# 3_-MCU.net
KiCad netlist of a schematic drawn in Altium Designer
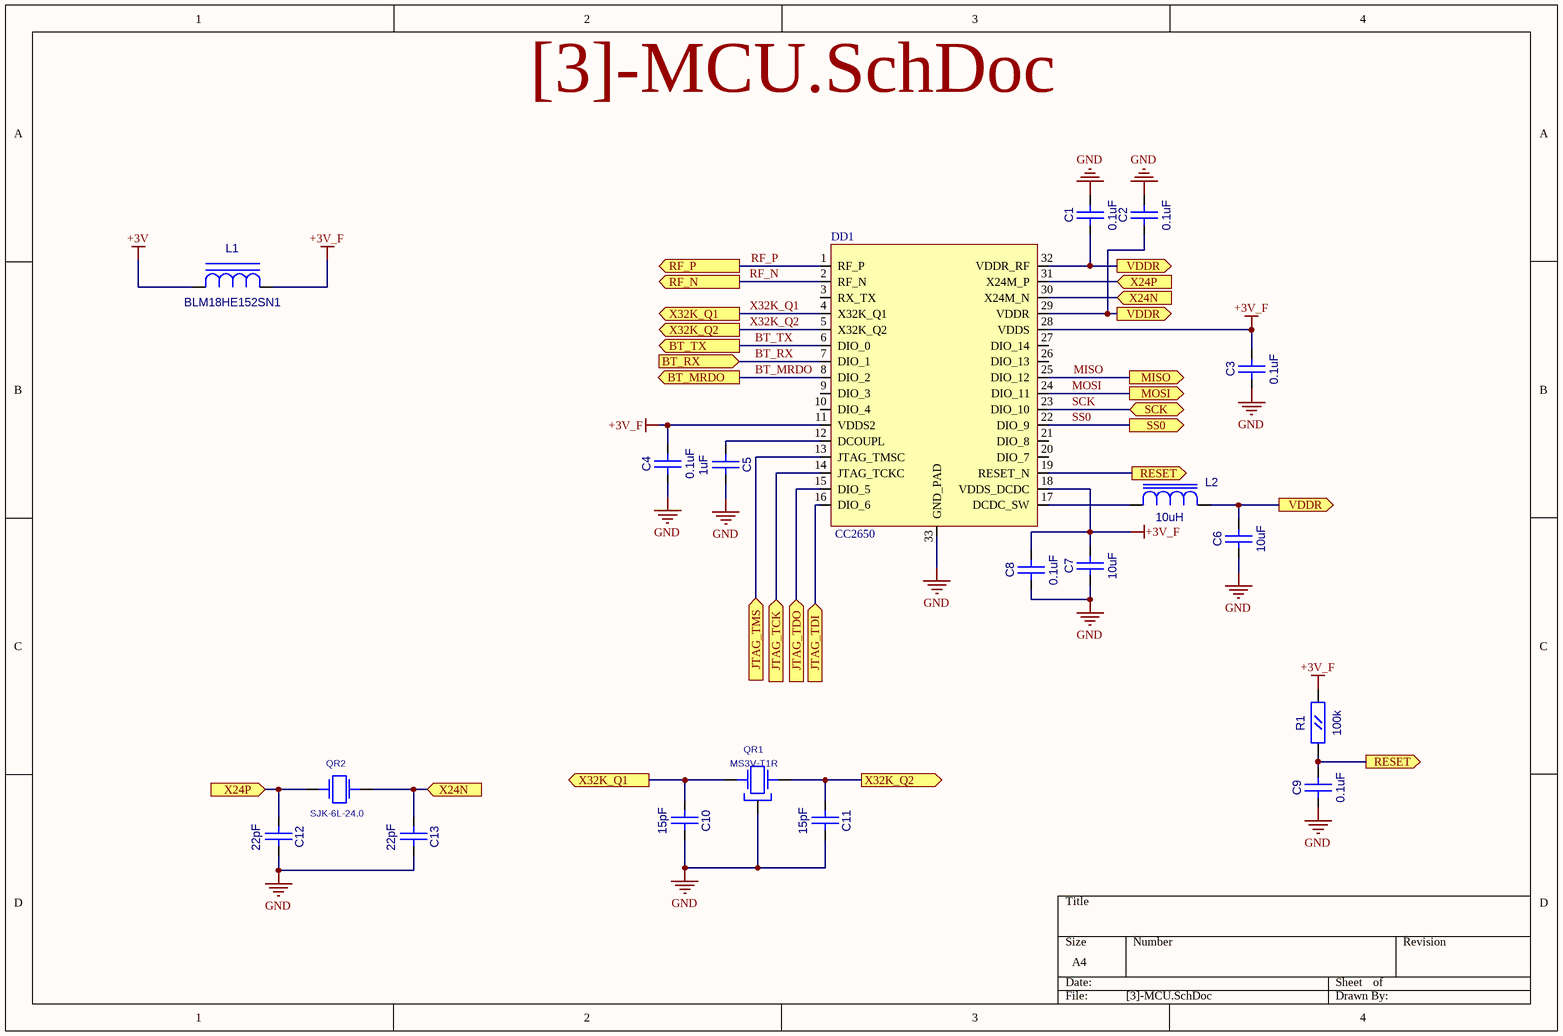
[diagram p0: [3]-MCU.SchDoc]

(export (version "E")
  (design (tool "Eeschema 10.0.6"))
  (components
    (comp (ref "C1")
      (value "0.1uF")
      (footprint "CC0603")
      (description "CC0603")
      (libsource (lib "gprs_modem_2") (part "CC0603"))
    )
    (comp (ref "C2")
      (value "0.1uF")
      (footprint "CC0603")
      (description "CC0603")
      (libsource (lib "gprs_modem_2") (part "CC0603"))
    )
    (comp (ref "C3")
      (value "0.1uF")
      (footprint "CC0603")
      (description "CC0603")
      (libsource (lib "gprs_modem_2") (part "CC0603"))
    )
    (comp (ref "C4")
      (value "0.1uF")
      (footprint "CC0603")
      (description "CC0603")
      (libsource (lib "gprs_modem_2") (part "CC0603"))
    )
    (comp (ref "C5")
      (value "1uF")
      (footprint "CC0603")
      (description "CC0603")
      (libsource (lib "gprs_modem_2") (part "CC0603"))
    )
    (comp (ref "C6")
      (value "10uF")
      (footprint "CC0805")
      (description "CC0805")
      (libsource (lib "gprs_modem_2") (part "CC0805"))
    )
    (comp (ref "C7")
      (value "10uF")
      (footprint "CC0805")
      (description "CC0805")
      (libsource (lib "gprs_modem_2") (part "CC0805"))
    )
    (comp (ref "C8")
      (value "0.1uF")
      (footprint "CC0603")
      (description "CC0603")
      (libsource (lib "gprs_modem_2") (part "CC0603"))
    )
    (comp (ref "C9")
      (value "0.1uF")
      (footprint "CC0603")
      (description "CC0603")
      (libsource (lib "gprs_modem_2") (part "CC0603"))
    )
    (comp (ref "C10")
      (value "15pF")
      (footprint "CC0603")
      (description "CC0603")
      (libsource (lib "gprs_modem_2") (part "CC0603"))
    )
    (comp (ref "C11")
      (value "15pF")
      (footprint "CC0603")
      (description "CC0603")
      (libsource (lib "gprs_modem_2") (part "CC0603"))
    )
    (comp (ref "C12")
      (value "22pF")
      (footprint "CC0603")
      (description "CC0603")
      (libsource (lib "gprs_modem_2") (part "CC0603"))
    )
    (comp (ref "C13")
      (value "22pF")
      (footprint "CC0603")
      (description "CC0603")
      (libsource (lib "gprs_modem_2") (part "CC0603"))
    )
    (comp (ref "DD1")
      (value "CC2650")
      (footprint "QFN32_TI")
      (description "CC2650RHBT")
      (libsource (lib "gprs_modem_2") (part "CC2650RHB"))
    )
    (comp (ref "L1")
      (value "BLM18HE152SN1")
      (footprint "L0603")
      (description "L0603")
      (libsource (lib "gprs_modem_2") (part "L0603"))
    )
    (comp (ref "L2")
      (value "10uH")
      (footprint "RC0805")
      (description "L0805")
      (libsource (lib "gprs_modem_2") (part "L0805"))
    )
    (comp (ref "QR1")
      (value "MS3V-T1R")
      (footprint "MS3V-T1R")
      (description "CRYSTAL_32768 Hz")
      (libsource (lib "gprs_modem_2") (part "MS3V-T1R"))
    )
    (comp (ref "QR2")
      (value "SJK-6L-24.0")
      (footprint "AC5032_2")
      (description "AC5032/2")
      (libsource (lib "gprs_modem_2") (part "AC5032_2"))
    )
    (comp (ref "R1")
      (value "100k")
      (footprint "RC0603")
      (description "RC0603")
      (libsource (lib "gprs_modem_2") (part "RC0603"))
    )
  )
  (nets
    (net (code "1") (name "+3V") (class "Default")
      (node (ref "L1") (pin "1") (pinfunction "A_1") (pintype "passive"))
    )
    (net (code "2") (name "+3V_F") (class "Default")
      (node (ref "C3") (pin "2") (pinfunction "B_2") (pintype "passive"))
      (node (ref "C4") (pin "2") (pinfunction "B_2") (pintype "passive"))
      (node (ref "C7") (pin "2") (pinfunction "B_2") (pintype "passive"))
      (node (ref "C8") (pin "2") (pinfunction "B_2") (pintype "passive"))
      (node (ref "DD1") (pin "11") (pinfunction "VDDS2_11") (pintype "passive"))
      (node (ref "DD1") (pin "18") (pinfunction "VDDS_DCDC_18") (pintype "passive"))
      (node (ref "DD1") (pin "28") (pinfunction "VDDS_28") (pintype "passive"))
      (node (ref "L1") (pin "2") (pinfunction "C_2") (pintype "passive"))
      (node (ref "R1") (pin "2") (pinfunction "B_2") (pintype "passive"))
    )
    (net (code "3") (name "/BT_MRDO") (class "Default")
      (node (ref "DD1") (pin "8") (pinfunction "DIO_2_8") (pintype "passive"))
    )
    (net (code "4") (name "/BT_RX") (class "Default")
      (node (ref "DD1") (pin "7") (pinfunction "DIO_1_7") (pintype "passive"))
    )
    (net (code "5") (name "/BT_TX") (class "Default")
      (node (ref "DD1") (pin "6") (pinfunction "DIO_0_6") (pintype "passive"))
    )
    (net (code "6") (name "/JTAG_TCK") (class "Default")
      (node (ref "DD1") (pin "14") (pinfunction "JTAG_TCKC_14") (pintype "passive"))
    )
    (net (code "7") (name "/JTAG_TDI") (class "Default")
      (node (ref "DD1") (pin "16") (pinfunction "DIO_6_16") (pintype "passive"))
    )
    (net (code "8") (name "/JTAG_TDO") (class "Default")
      (node (ref "DD1") (pin "15") (pinfunction "DIO_5_15") (pintype "passive"))
    )
    (net (code "9") (name "/JTAG_TMS") (class "Default")
      (node (ref "DD1") (pin "13") (pinfunction "JTAG_TMSC_13") (pintype "passive"))
    )
    (net (code "10") (name "/MISO") (class "Default")
      (node (ref "DD1") (pin "25") (pinfunction "DIO_12_25") (pintype "passive"))
    )
    (net (code "11") (name "/MOSI") (class "Default")
      (node (ref "DD1") (pin "24") (pinfunction "DIO_11_24") (pintype "passive"))
    )
    (net (code "12") (name "/RESET") (class "Default")
      (node (ref "C9") (pin "2") (pinfunction "B_2") (pintype "passive"))
      (node (ref "DD1") (pin "19") (pinfunction "RESET_N_19") (pintype "passive"))
      (node (ref "R1") (pin "1") (pinfunction "A_1") (pintype "passive"))
    )
    (net (code "13") (name "/RF_N") (class "Default")
      (node (ref "DD1") (pin "2") (pinfunction "RF_N_2") (pintype "passive"))
    )
    (net (code "14") (name "/RF_P") (class "Default")
      (node (ref "DD1") (pin "1") (pinfunction "RF_P_1") (pintype "passive"))
    )
    (net (code "15") (name "/SCK") (class "Default")
      (node (ref "DD1") (pin "23") (pinfunction "DIO_10_23") (pintype "passive"))
    )
    (net (code "16") (name "/SS0") (class "Default")
      (node (ref "DD1") (pin "22") (pinfunction "DIO_9_22") (pintype "passive"))
    )
    (net (code "17") (name "/VDDR") (class "Default")
      (node (ref "C1") (pin "1") (pinfunction "A_1") (pintype "passive"))
      (node (ref "C2") (pin "1") (pinfunction "A_1") (pintype "passive"))
      (node (ref "C6") (pin "2") (pinfunction "B_2") (pintype "passive"))
      (node (ref "DD1") (pin "29") (pinfunction "VDDR_29") (pintype "passive"))
      (node (ref "DD1") (pin "32") (pinfunction "VDDR_RF_32") (pintype "passive"))
      (node (ref "L2") (pin "2") (pinfunction "B_2") (pintype "passive"))
    )
    (net (code "18") (name "/X24N") (class "Default")
      (node (ref "C13") (pin "1") (pinfunction "A_1") (pintype "passive"))
      (node (ref "DD1") (pin "30") (pinfunction "X24M_N_30") (pintype "passive"))
      (node (ref "QR2") (pin "2") (pintype "passive"))
    )
    (net (code "19") (name "/X24P") (class "Default")
      (node (ref "C12") (pin "1") (pinfunction "A_1") (pintype "passive"))
      (node (ref "DD1") (pin "31") (pinfunction "X24M_P_31") (pintype "passive"))
      (node (ref "QR2") (pin "1") (pintype "passive"))
    )
    (net (code "20") (name "/X32K_Q1") (class "Default")
      (node (ref "C10") (pin "1") (pinfunction "A_1") (pintype "passive"))
      (node (ref "DD1") (pin "4") (pinfunction "X32K_Q1_4") (pintype "passive"))
      (node (ref "QR1") (pin "2") (pinfunction "X2_2") (pintype "passive"))
    )
    (net (code "21") (name "/X32K_Q2") (class "Default")
      (node (ref "C11") (pin "1") (pinfunction "A_1") (pintype "passive"))
      (node (ref "DD1") (pin "5") (pinfunction "X32K_Q2_5") (pintype "passive"))
      (node (ref "QR1") (pin "1") (pinfunction "X1_1") (pintype "passive"))
    )
    (net (code "22") (name "GND") (class "Default")
      (node (ref "C1") (pin "2") (pinfunction "B_2") (pintype "passive"))
      (node (ref "C10") (pin "2") (pinfunction "B_2") (pintype "passive"))
      (node (ref "C11") (pin "2") (pinfunction "B_2") (pintype "passive"))
      (node (ref "C12") (pin "2") (pinfunction "B_2") (pintype "passive"))
      (node (ref "C13") (pin "2") (pinfunction "B_2") (pintype "passive"))
      (node (ref "C2") (pin "2") (pinfunction "B_2") (pintype "passive"))
      (node (ref "C3") (pin "1") (pinfunction "A_1") (pintype "passive"))
      (node (ref "C4") (pin "1") (pinfunction "A_1") (pintype "passive"))
      (node (ref "C5") (pin "2") (pinfunction "B_2") (pintype "passive"))
      (node (ref "C6") (pin "1") (pinfunction "A_1") (pintype "passive"))
      (node (ref "C7") (pin "1") (pinfunction "A_1") (pintype "passive"))
      (node (ref "C8") (pin "1") (pinfunction "A_1") (pintype "passive"))
      (node (ref "C9") (pin "1") (pinfunction "A_1") (pintype "passive"))
      (node (ref "DD1") (pin "33") (pinfunction "GND_PAD_33") (pintype "passive"))
      (node (ref "QR1") (pin "3") (pinfunction "3_3") (pintype "passive"))
    )
    (net (code "23") (name "Net-(C5-A)") (class "Default")
      (node (ref "C5") (pin "1") (pinfunction "A_1") (pintype "passive"))
      (node (ref "DD1") (pin "12") (pinfunction "DCOUPL_12") (pintype "passive"))
    )
    (net (code "24") (name "Net-(DD1-DCDC_SW)") (class "Default")
      (node (ref "DD1") (pin "17") (pinfunction "DCDC_SW_17") (pintype "passive"))
      (node (ref "L2") (pin "1") (pinfunction "A_1") (pintype "passive"))
    )
    (net (code "25") (name "unconnected-(DD1-DIO_3-Pad9)") (class "Default")
      (node (ref "DD1") (pin "9") (pinfunction "DIO_3_9") (pintype "passive"))
    )
    (net (code "26") (name "unconnected-(DD1-DIO_4-Pad10)") (class "Default")
      (node (ref "DD1") (pin "10") (pinfunction "DIO_4_10") (pintype "passive"))
    )
    (net (code "27") (name "unconnected-(DD1-DIO_7-Pad20)") (class "Default")
      (node (ref "DD1") (pin "20") (pinfunction "DIO_7_20") (pintype "passive"))
    )
    (net (code "28") (name "unconnected-(DD1-DIO_8-Pad21)") (class "Default")
      (node (ref "DD1") (pin "21") (pinfunction "DIO_8_21") (pintype "passive"))
    )
    (net (code "29") (name "unconnected-(DD1-DIO_13-Pad26)") (class "Default")
      (node (ref "DD1") (pin "26") (pinfunction "DIO_13_26") (pintype "passive"))
    )
    (net (code "30") (name "unconnected-(DD1-DIO_14-Pad27)") (class "Default")
      (node (ref "DD1") (pin "27") (pinfunction "DIO_14_27") (pintype "passive"))
    )
    (net (code "31") (name "unconnected-(DD1-RX_TX-Pad3)") (class "Default")
      (node (ref "DD1") (pin "3") (pinfunction "RX_TX_3") (pintype "passive"))
    )
  )
)
